# Moses_Ft__Creamer.net
KiCad netlist of a schematic drawn in EAGLE
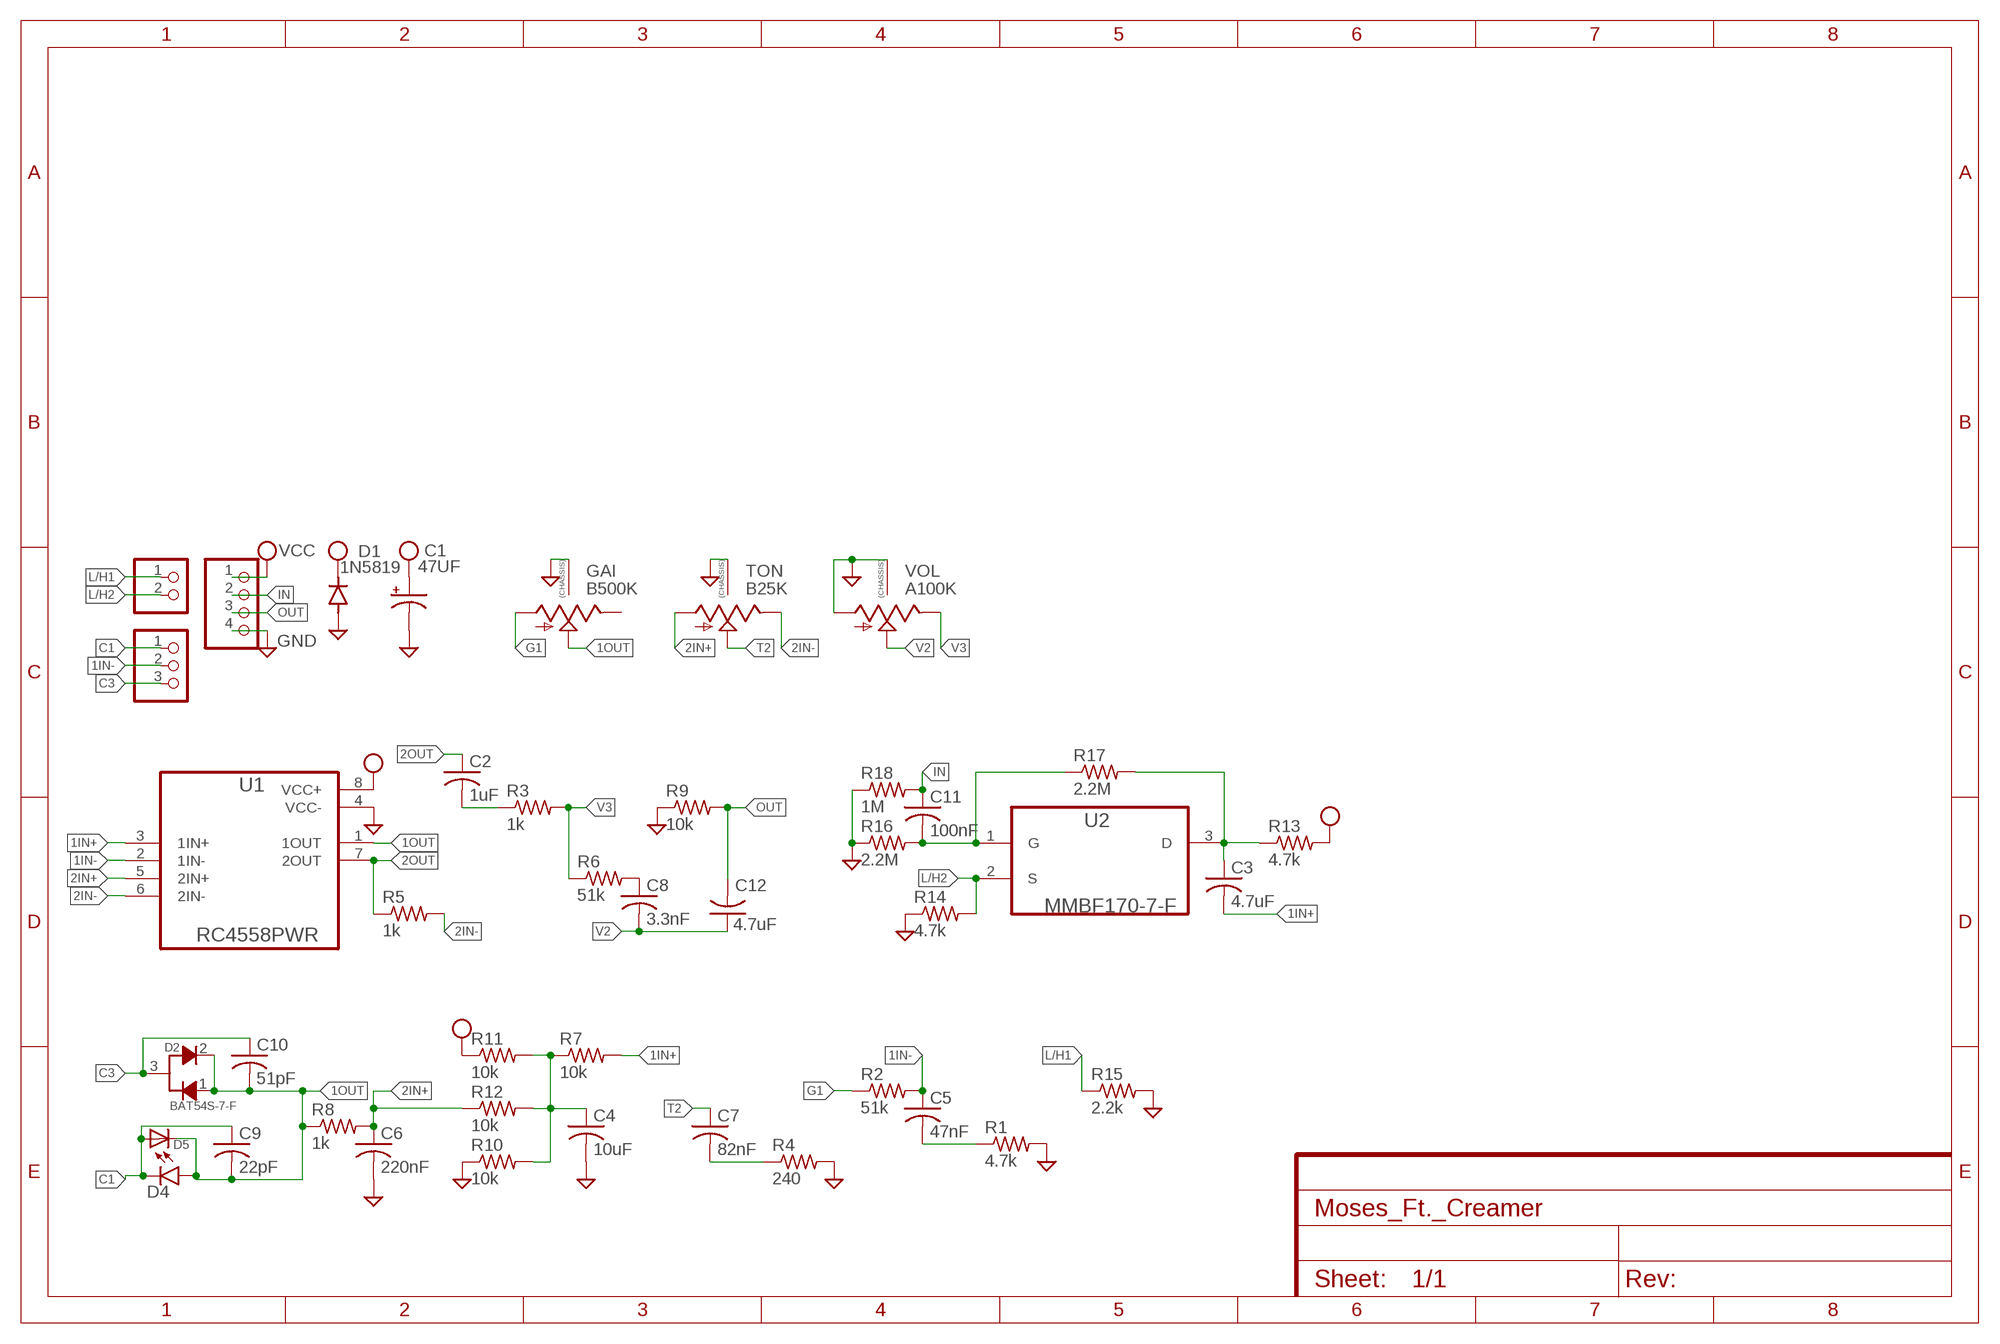
[diagram p0: schematic, sheet 1]

(export (version "E")
  (design (tool "Eeschema 10.0.6"))
  (components
    (comp (ref "C1")
      (value "47UF")
      (footprint "eagle-import:PAN_B_SMD+THRU")
      (libsource (lib "eagle-import") (part "CAP_SMD+THRUPAN_B"))
    )
    (comp (ref "C2")
      (value "1uF")
      (footprint "eagle-import:C0805")
      (libsource (lib "eagle-import") (part "adafruit_420_C-USC0805"))
    )
    (comp (ref "C3")
      (value "4.7uF")
      (footprint "eagle-import:C1206")
      (libsource (lib "eagle-import") (part "adafruit_420_C-USC1206"))
    )
    (comp (ref "C4")
      (value "10uF")
      (footprint "eagle-import:C1206")
      (libsource (lib "eagle-import") (part "adafruit_420_C-USC1206"))
    )
    (comp (ref "C5")
      (value "47nF")
      (footprint "eagle-import:C0603")
      (libsource (lib "eagle-import") (part "C-USC0603"))
    )
    (comp (ref "C6")
      (value "220nF")
      (footprint "eagle-import:C0603")
      (libsource (lib "eagle-import") (part "C-USC0603"))
    )
    (comp (ref "C7")
      (value "82nF")
      (footprint "eagle-import:C0603")
      (libsource (lib "eagle-import") (part "C-USC0603"))
    )
    (comp (ref "C8")
      (value "3.3nF")
      (footprint "eagle-import:C0603")
      (libsource (lib "eagle-import") (part "C-USC0603"))
    )
    (comp (ref "C9")
      (value "22pF")
      (footprint "eagle-import:C0603")
      (libsource (lib "eagle-import") (part "C-USC0603"))
    )
    (comp (ref "C10")
      (value "51pF")
      (footprint "eagle-import:C0603")
      (libsource (lib "eagle-import") (part "C-USC0603"))
    )
    (comp (ref "C11")
      (value "100nF")
      (footprint "eagle-import:C0603")
      (libsource (lib "eagle-import") (part "C-USC0603"))
    )
    (comp (ref "C12")
      (value "4.7uF")
      (footprint "eagle-import:C1206")
      (libsource (lib "eagle-import") (part "adafruit_420_C-USC1206"))
    )
    (comp (ref "D1")
      (value "1N5819")
      (footprint "eagle-import:SOD123")
      (libsource (lib "eagle-import") (part "DIODE-SOD123"))
    )
    (comp (ref "D2")
      (value "BAT54S-7-F")
      (footprint "eagle-import:SOT23-3")
      (fields
        (field (name "DIGIKEY_PART_NUMBER") "BAT54S-FDITR-ND")
        (field (name "MANUFACTURER") "Diodes Incorporated")
        (field (name "CREATED_BY") "PCBLayout.com")
      )
      (libsource (lib "eagle-import") (part "BAT54S-7-F"))
    )
    (comp (ref "D4")
      (value "LED0603")
      (footprint "eagle-import:LED-0603")
      (libsource (lib "eagle-import") (part "LED0603"))
    )
    (comp (ref "D5")
      (value "DIODESOD-123")
      (footprint "eagle-import:SOD-123")
      (libsource (lib "eagle-import") (part "DIODESOD-123"))
    )
    (comp (ref "GAI")
      (value "B500K")
      (footprint "eagle-import:9MM_SNAP-IN_POT")
      (libsource (lib "eagle-import") (part "9MM_SNAP-IN_POT_CHASSIS"))
    )
    (comp (ref "JP1")
      (value "PINHD-1X4")
      (footprint "eagle-import:1X04")
      (libsource (lib "eagle-import") (part "PINHD-1X4"))
    )
    (comp (ref "JP2")
      (value "PINHD-1X2")
      (footprint "eagle-import:1X02")
      (libsource (lib "eagle-import") (part "PINHD-1X2"))
    )
    (comp (ref "JP3")
      (value "PINHD-1X3")
      (footprint "eagle-import:1X03")
      (libsource (lib "eagle-import") (part "PINHD-1X3"))
    )
    (comp (ref "R1")
      (value "4.7k")
      (footprint "eagle-import:R0603")
      (libsource (lib "eagle-import") (part "R-US_R0603"))
    )
    (comp (ref "R2")
      (value "51k")
      (footprint "eagle-import:R0603")
      (libsource (lib "eagle-import") (part "R-US_R0603"))
    )
    (comp (ref "R3")
      (value "1k")
      (footprint "eagle-import:R0603")
      (libsource (lib "eagle-import") (part "R-US_R0603"))
    )
    (comp (ref "R4")
      (value "240")
      (footprint "eagle-import:R0603")
      (libsource (lib "eagle-import") (part "R-US_R0603"))
    )
    (comp (ref "R5")
      (value "1k")
      (footprint "eagle-import:R0603")
      (libsource (lib "eagle-import") (part "R-US_R0603"))
    )
    (comp (ref "R6")
      (value "51k")
      (footprint "eagle-import:R0603")
      (libsource (lib "eagle-import") (part "R-US_R0603"))
    )
    (comp (ref "R7")
      (value "10k")
      (footprint "eagle-import:R0603")
      (libsource (lib "eagle-import") (part "R-US_R0603"))
    )
    (comp (ref "R8")
      (value "1k")
      (footprint "eagle-import:R0603")
      (libsource (lib "eagle-import") (part "R-US_R0603"))
    )
    (comp (ref "R9")
      (value "10k")
      (footprint "eagle-import:R0603")
      (libsource (lib "eagle-import") (part "R-US_R0603"))
    )
    (comp (ref "R10")
      (value "10k")
      (footprint "eagle-import:R0603")
      (libsource (lib "eagle-import") (part "R-US_R0603"))
    )
    (comp (ref "R11")
      (value "10k")
      (footprint "eagle-import:R0603")
      (libsource (lib "eagle-import") (part "R-US_R0603"))
    )
    (comp (ref "R12")
      (value "10k")
      (footprint "eagle-import:R0603")
      (libsource (lib "eagle-import") (part "R-US_R0603"))
    )
    (comp (ref "R13")
      (value "4.7k")
      (footprint "eagle-import:R0603")
      (libsource (lib "eagle-import") (part "R-US_R0603"))
    )
    (comp (ref "R14")
      (value "4.7k")
      (footprint "eagle-import:R0603")
      (libsource (lib "eagle-import") (part "R-US_R0603"))
    )
    (comp (ref "R15")
      (value "2.2k")
      (footprint "eagle-import:R0603")
      (libsource (lib "eagle-import") (part "R-US_R0603"))
    )
    (comp (ref "R16")
      (value "2.2M")
      (footprint "eagle-import:R0603")
      (libsource (lib "eagle-import") (part "R-US_R0603"))
    )
    (comp (ref "R17")
      (value "2.2M")
      (footprint "eagle-import:R0603")
      (libsource (lib "eagle-import") (part "R-US_R0603"))
    )
    (comp (ref "R18")
      (value "1M")
      (footprint "eagle-import:R0603")
      (libsource (lib "eagle-import") (part "R-US_R0603"))
    )
    (comp (ref "TON")
      (value "B25K")
      (footprint "eagle-import:9MM_SNAP-IN_POT")
      (libsource (lib "eagle-import") (part "9MM_SNAP-IN_POT_CHASSIS"))
    )
    (comp (ref "U1")
      (value "RC4558PWR")
      (footprint "eagle-import:SOP65P640X120-8N")
      (fields (field (name "MF") "Texas Instruments"))
      (libsource (lib "eagle-import") (part "RC4558PWR"))
    )
    (comp (ref "U2")
      (value "MMBF170-7-F")
      (footprint "eagle-import:SOT103P240X110-3N")
      (fields (field (name "MF") "Diodes Inc."))
      (libsource (lib "eagle-import") (part "MMBF170-7-F"))
    )
    (comp (ref "VOL")
      (value "A100K")
      (footprint "eagle-import:9MM_SNAP-IN_POT")
      (libsource (lib "eagle-import") (part "9MM_SNAP-IN_POT_CHASSIS"))
    )
  )
  (nets
    (net (code "1") (name "1IN+") (class "Default")
      (node (ref "C3") (pin "2") (pinfunction "2_2") (pintype "passive"))
      (node (ref "R7") (pin "2") (pinfunction "2_2") (pintype "passive"))
      (node (ref "U1") (pin "3") (pinfunction "1IN+_3") (pintype "input"))
    )
    (net (code "2") (name "1IN-") (class "Default")
      (node (ref "C5") (pin "1") (pinfunction "1_1") (pintype "passive"))
      (node (ref "JP3") (pin "2") (pinfunction "2_2") (pintype "passive"))
      (node (ref "R2") (pin "2") (pinfunction "2_2") (pintype "passive"))
      (node (ref "U1") (pin "2") (pinfunction "1IN-_2") (pintype "input"))
    )
    (net (code "3") (name "1OUT") (class "Default")
      (node (ref "C10") (pin "2") (pinfunction "2_2") (pintype "passive"))
      (node (ref "C9") (pin "2") (pinfunction "2_2") (pintype "passive"))
      (node (ref "D2") (pin "1") (pinfunction "1_1") (pintype "passive"))
      (node (ref "D2") (pin "2") (pinfunction "2_2") (pintype "passive"))
      (node (ref "D4") (pin "A") (pinfunction "A_A") (pintype "passive"))
      (node (ref "D5") (pin "C") (pinfunction "C_C") (pintype "passive"))
      (node (ref "GAI") (pin "2") (pinfunction "S_2") (pintype "passive"))
      (node (ref "R8") (pin "1") (pinfunction "1_1") (pintype "passive"))
      (node (ref "U1") (pin "1") (pinfunction "1OUT_1") (pintype "output"))
    )
    (net (code "4") (name "2IN+") (class "Default")
      (node (ref "C6") (pin "1") (pinfunction "1_1") (pintype "passive"))
      (node (ref "R12") (pin "1") (pinfunction "1_1") (pintype "passive"))
      (node (ref "R8") (pin "2") (pinfunction "2_2") (pintype "passive"))
      (node (ref "TON") (pin "1") (pinfunction "A_1") (pintype "passive"))
      (node (ref "U1") (pin "5") (pinfunction "2IN+_5") (pintype "input"))
    )
    (net (code "5") (name "2IN-") (class "Default")
      (node (ref "R5") (pin "2") (pinfunction "2_2") (pintype "passive"))
      (node (ref "TON") (pin "3") (pinfunction "E_3") (pintype "passive"))
      (node (ref "U1") (pin "6") (pinfunction "2IN-_6") (pintype "input"))
    )
    (net (code "6") (name "2OUT") (class "Default")
      (node (ref "C2") (pin "1") (pinfunction "1_1") (pintype "passive"))
      (node (ref "R5") (pin "1") (pinfunction "1_1") (pintype "passive"))
      (node (ref "U1") (pin "7") (pinfunction "2OUT_7") (pintype "output"))
    )
    (net (code "7") (name "C1") (class "Default")
      (node (ref "C9") (pin "1") (pinfunction "1_1") (pintype "passive"))
      (node (ref "D4") (pin "C") (pinfunction "C_C") (pintype "passive"))
      (node (ref "D5") (pin "A") (pinfunction "A_A") (pintype "passive"))
      (node (ref "JP3") (pin "1") (pinfunction "1_1") (pintype "passive"))
    )
    (net (code "8") (name "C3") (class "Default")
      (node (ref "C10") (pin "1") (pinfunction "1_1") (pintype "passive"))
      (node (ref "D2") (pin "3") (pinfunction "3_3") (pintype "passive"))
      (node (ref "JP3") (pin "3") (pinfunction "3_3") (pintype "passive"))
    )
    (net (code "9") (name "G1") (class "Default")
      (node (ref "GAI") (pin "1") (pinfunction "A_1") (pintype "passive"))
      (node (ref "R2") (pin "1") (pinfunction "1_1") (pintype "passive"))
    )
    (net (code "10") (name "GND") (class "Default")
      (node (ref "C1") (pin "-") (pinfunction "-_-") (pintype "passive"))
      (node (ref "C1") (pin "--") (pinfunction "-_--") (pintype "passive"))
      (node (ref "C4") (pin "2") (pinfunction "2_2") (pintype "passive"))
      (node (ref "C6") (pin "2") (pinfunction "2_2") (pintype "passive"))
      (node (ref "D1") (pin "A") (pinfunction "A_A") (pintype "passive"))
      (node (ref "GAI") (pin "CHASSIS1") (pinfunction "P$1_CHASSIS1") (pintype "passive"))
      (node (ref "GAI") (pin "CHASSIS2") (pinfunction "P$1_CHASSIS2") (pintype "passive"))
      (node (ref "JP1") (pin "4") (pinfunction "4_4") (pintype "passive"))
      (node (ref "R1") (pin "2") (pinfunction "2_2") (pintype "passive"))
      (node (ref "R10") (pin "1") (pinfunction "1_1") (pintype "passive"))
      (node (ref "R14") (pin "1") (pinfunction "1_1") (pintype "passive"))
      (node (ref "R15") (pin "2") (pinfunction "2_2") (pintype "passive"))
      (node (ref "R16") (pin "1") (pinfunction "1_1") (pintype "passive"))
      (node (ref "R18") (pin "1") (pinfunction "1_1") (pintype "passive"))
      (node (ref "R4") (pin "2") (pinfunction "2_2") (pintype "passive"))
      (node (ref "R9") (pin "1") (pinfunction "1_1") (pintype "passive"))
      (node (ref "TON") (pin "CHASSIS1") (pinfunction "P$1_CHASSIS1") (pintype "passive"))
      (node (ref "TON") (pin "CHASSIS2") (pinfunction "P$1_CHASSIS2") (pintype "passive"))
      (node (ref "U1") (pin "4") (pinfunction "VCC-_4") (pintype "power_in"))
      (node (ref "VOL") (pin "1") (pinfunction "A_1") (pintype "passive"))
      (node (ref "VOL") (pin "CHASSIS1") (pinfunction "P$1_CHASSIS1") (pintype "passive"))
      (node (ref "VOL") (pin "CHASSIS2") (pinfunction "P$1_CHASSIS2") (pintype "passive"))
    )
    (net (code "11") (name "IN") (class "Default")
      (node (ref "C11") (pin "1") (pinfunction "1_1") (pintype "passive"))
      (node (ref "JP1") (pin "2") (pinfunction "2_2") (pintype "passive"))
      (node (ref "R18") (pin "2") (pinfunction "2_2") (pintype "passive"))
    )
    (net (code "12") (name "L{slash}H1") (class "Default")
      (node (ref "JP2") (pin "1") (pinfunction "1_1") (pintype "passive"))
      (node (ref "R15") (pin "1") (pinfunction "1_1") (pintype "passive"))
    )
    (net (code "13") (name "L{slash}H2") (class "Default")
      (node (ref "JP2") (pin "2") (pinfunction "2_2") (pintype "passive"))
      (node (ref "R14") (pin "2") (pinfunction "2_2") (pintype "passive"))
      (node (ref "U2") (pin "2") (pinfunction "S_2") (pintype "passive"))
    )
    (net (code "14") (name "Net-(C2-Pad2)") (class "Default")
      (node (ref "C2") (pin "2") (pinfunction "2_2") (pintype "passive"))
      (node (ref "R3") (pin "1") (pinfunction "1_1") (pintype "passive"))
    )
    (net (code "15") (name "Net-(C4-Pad1)") (class "Default")
      (node (ref "C4") (pin "1") (pinfunction "1_1") (pintype "passive"))
      (node (ref "R10") (pin "2") (pinfunction "2_2") (pintype "passive"))
      (node (ref "R11") (pin "2") (pinfunction "2_2") (pintype "passive"))
      (node (ref "R12") (pin "2") (pinfunction "2_2") (pintype "passive"))
      (node (ref "R7") (pin "1") (pinfunction "1_1") (pintype "passive"))
    )
    (net (code "16") (name "Net-(C5-Pad2)") (class "Default")
      (node (ref "C5") (pin "2") (pinfunction "2_2") (pintype "passive"))
      (node (ref "R1") (pin "1") (pinfunction "1_1") (pintype "passive"))
    )
    (net (code "17") (name "Net-(C7-Pad2)") (class "Default")
      (node (ref "C7") (pin "2") (pinfunction "2_2") (pintype "passive"))
      (node (ref "R4") (pin "1") (pinfunction "1_1") (pintype "passive"))
    )
    (net (code "18") (name "Net-(C8-Pad1)") (class "Default")
      (node (ref "C8") (pin "1") (pinfunction "1_1") (pintype "passive"))
      (node (ref "R6") (pin "2") (pinfunction "2_2") (pintype "passive"))
    )
    (net (code "19") (name "Net-(U2-D)") (class "Default")
      (node (ref "C3") (pin "1") (pinfunction "1_1") (pintype "passive"))
      (node (ref "R13") (pin "1") (pinfunction "1_1") (pintype "passive"))
      (node (ref "R17") (pin "2") (pinfunction "2_2") (pintype "passive"))
      (node (ref "U2") (pin "3") (pinfunction "D_3") (pintype "output"))
    )
    (net (code "20") (name "Net-(U2-G)") (class "Default")
      (node (ref "C11") (pin "2") (pinfunction "2_2") (pintype "passive"))
      (node (ref "R16") (pin "2") (pinfunction "2_2") (pintype "passive"))
      (node (ref "R17") (pin "1") (pinfunction "1_1") (pintype "passive"))
      (node (ref "U2") (pin "1") (pinfunction "G_1") (pintype "input"))
    )
    (net (code "21") (name "OUT") (class "Default")
      (node (ref "C12") (pin "2") (pinfunction "2_2") (pintype "passive"))
      (node (ref "JP1") (pin "3") (pinfunction "3_3") (pintype "passive"))
      (node (ref "R9") (pin "2") (pinfunction "2_2") (pintype "passive"))
    )
    (net (code "22") (name "T2") (class "Default")
      (node (ref "C7") (pin "1") (pinfunction "1_1") (pintype "passive"))
      (node (ref "TON") (pin "2") (pinfunction "S_2") (pintype "passive"))
    )
    (net (code "23") (name "V2") (class "Default")
      (node (ref "C12") (pin "1") (pinfunction "1_1") (pintype "passive"))
      (node (ref "C8") (pin "2") (pinfunction "2_2") (pintype "passive"))
      (node (ref "VOL") (pin "2") (pinfunction "S_2") (pintype "passive"))
    )
    (net (code "24") (name "V3") (class "Default")
      (node (ref "R3") (pin "2") (pinfunction "2_2") (pintype "passive"))
      (node (ref "R6") (pin "1") (pinfunction "1_1") (pintype "passive"))
      (node (ref "VOL") (pin "3") (pinfunction "E_3") (pintype "passive"))
    )
    (net (code "25") (name "VCC") (class "Default")
      (node (ref "C1") (pin "+") (pinfunction "+_+") (pintype "passive"))
      (node (ref "C1") (pin "++") (pinfunction "+_++") (pintype "passive"))
      (node (ref "D1") (pin "C") (pinfunction "C_C") (pintype "passive"))
      (node (ref "JP1") (pin "1") (pinfunction "1_1") (pintype "passive"))
      (node (ref "R11") (pin "1") (pinfunction "1_1") (pintype "passive"))
      (node (ref "R13") (pin "2") (pinfunction "2_2") (pintype "passive"))
      (node (ref "U1") (pin "8") (pinfunction "VCC+_8") (pintype "power_in"))
    )
    (net (code "26") (name "unconnected-(GAI-E-Pad3)") (class "Default")
      (node (ref "GAI") (pin "3") (pinfunction "E_3") (pintype "passive"))
    )
  )
)
